# Sheet1.net
KiCad netlist of a schematic drawn in Altium Designer
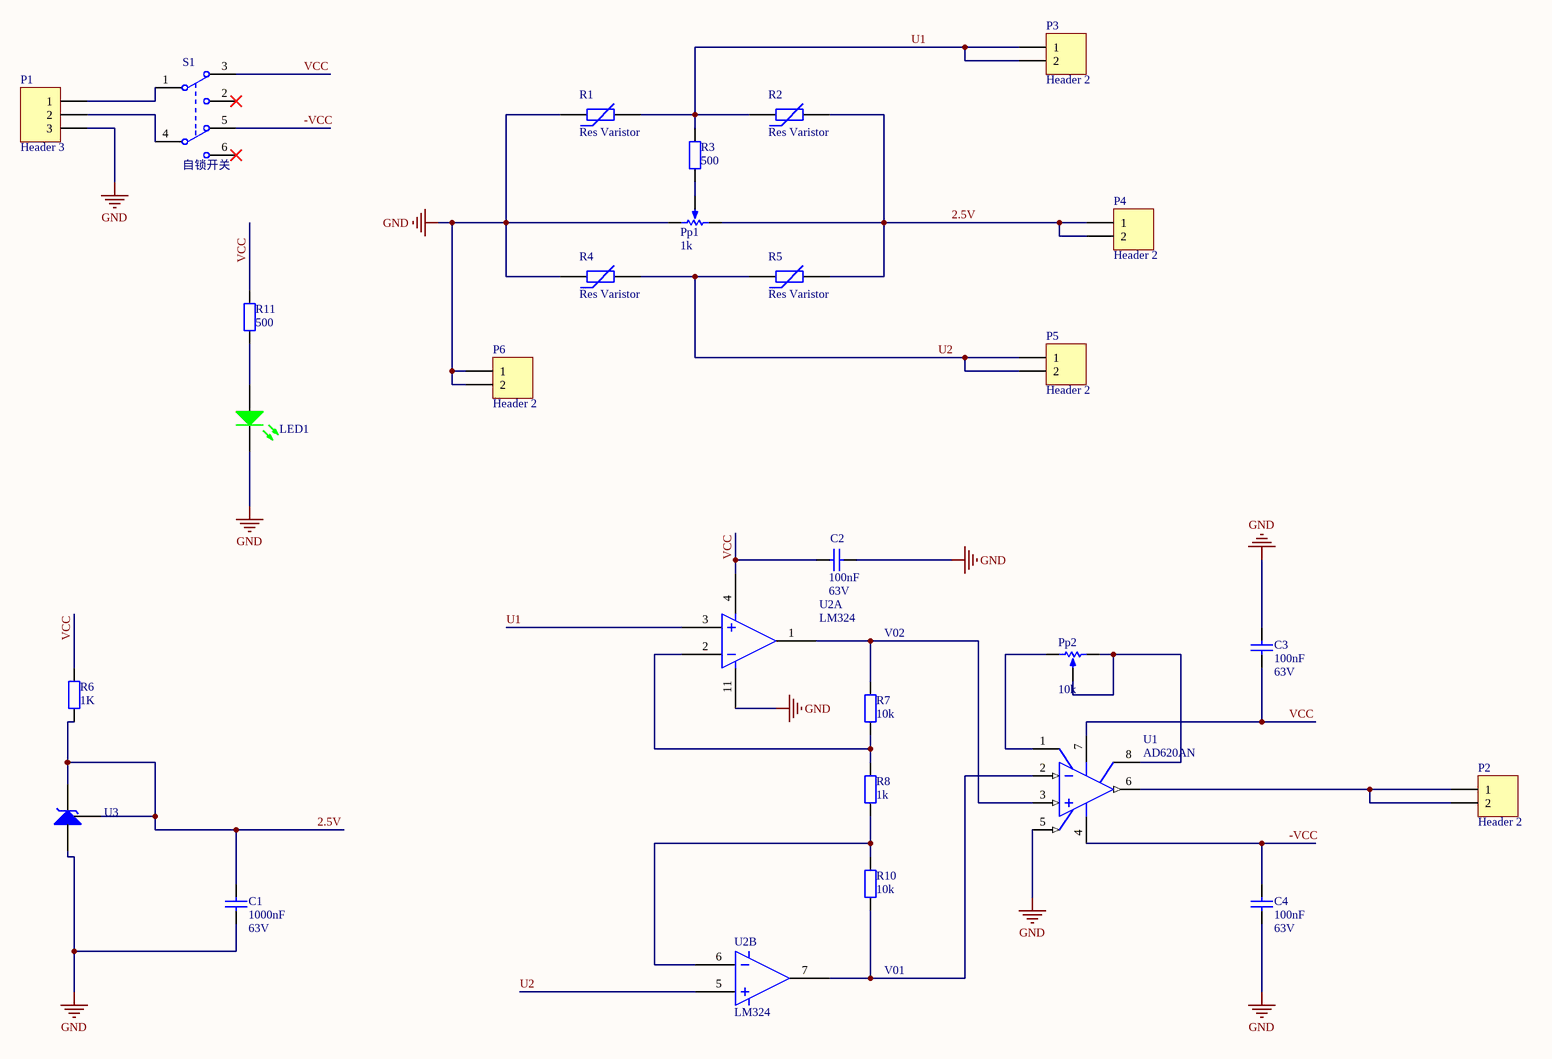
[diagram p0: Sheet1.SchDoc]

(export (version "E")
  (design (tool "Eeschema 10.0.6"))
  (components
    (comp (ref "C1")
      (value "1000nF")
      (footprint "Capacitor-Disk-Middle")
      (description "CBB聚乙烯薄膜电容")
      (fields
        (field (name "VOLTAGE") "63V")
        (field (name "Comment") "Cap Nicklon")
        (field (name "PUBLISHER") "Altium Limited")
      )
      (libsource (lib "02-Miscellaneous_Devices_ZSF_Library") (part "Cap Nicklon"))
    )
    (comp (ref "C2")
      (value "100nF")
      (footprint "Capacitor-Disk-Middle")
      (description "CBB聚乙烯薄膜电容")
      (fields
        (field (name "VOLTAGE") "63V")
        (field (name "Comment") "Cap Nicklon")
        (field (name "PUBLISHER") "Altium Limited")
      )
      (libsource (lib "02-Miscellaneous_Devices_ZSF_Library") (part "Cap Nicklon"))
    )
    (comp (ref "C3")
      (value "100nF")
      (footprint "Capacitor-Disk-Middle")
      (description "CBB聚乙烯薄膜电容")
      (fields
        (field (name "VOLTAGE") "63V")
        (field (name "Comment") "Cap Nicklon")
        (field (name "PUBLISHER") "Altium Limited")
      )
      (libsource (lib "02-Miscellaneous_Devices_ZSF_Library") (part "Cap Nicklon"))
    )
    (comp (ref "C4")
      (value "100nF")
      (footprint "Capacitor-Disk-Middle")
      (description "CBB聚乙烯薄膜电容")
      (fields
        (field (name "VOLTAGE") "63V")
        (field (name "Comment") "Cap Nicklon")
        (field (name "PUBLISHER") "Altium Limited")
      )
      (libsource (lib "02-Miscellaneous_Devices_ZSF_Library") (part "Cap Nicklon"))
    )
    (comp (ref "LED1")
      (value "LED-3-G")
      (footprint "LED-R3-H5-SINGLE-G")
      (description "Typical INFRARED GaAs LED")
      (fields (field (name "PUBLISHER") "Altium Limited"))
      (libsource (lib "03-EButterflyIntegratedLibrary") (part "LED-3-G"))
    )
    (comp (ref "P1")
      (value "Header 3")
      (footprint "HX2.54-3")
      (description "Header, 3-Pin")
      (fields (field (name "PUBLISHER") "Altium Limited"))
      (libsource (lib "03-EButterflyIntegratedLibrary") (part "Header 3"))
    )
    (comp (ref "P2")
      (value "Header 2")
      (footprint "HDR1X2")
      (description "Header, 2-Pin")
      (fields (field (name "PUBLISHER") "Altium Limited"))
      (libsource (lib "03-EButterflyIntegratedLibrary") (part "Header 2"))
    )
    (comp (ref "P3")
      (value "Header 2")
      (footprint "HDR1X2")
      (description "Header, 2-Pin")
      (fields (field (name "PUBLISHER") "Altium Limited"))
      (libsource (lib "03-EButterflyIntegratedLibrary") (part "Header 2"))
    )
    (comp (ref "P4")
      (value "Header 2")
      (footprint "HDR1X2")
      (description "Header, 2-Pin")
      (fields (field (name "PUBLISHER") "Altium Limited"))
      (libsource (lib "03-EButterflyIntegratedLibrary") (part "Header 2"))
    )
    (comp (ref "P5")
      (value "Header 2")
      (footprint "HDR1X2")
      (description "Header, 2-Pin")
      (fields (field (name "PUBLISHER") "Altium Limited"))
      (libsource (lib "03-EButterflyIntegratedLibrary") (part "Header 2"))
    )
    (comp (ref "P6")
      (value "Header 2")
      (footprint "HDR1X2")
      (description "Header, 2-Pin")
      (fields (field (name "PUBLISHER") "Altium Limited"))
      (libsource (lib "03-EButterflyIntegratedLibrary") (part "Header 2"))
    )
    (comp (ref "Pp1")
      (value "1k")
      (footprint "RP_3296")
      (description "3296电位器")
      (libsource (lib "02-Miscellaneous_Devices_ZSF_Library") (part "RP_3296"))
    )
    (comp (ref "Pp2")
      (value "10k")
      (footprint "RP_3296")
      (description "3296电位器")
      (libsource (lib "02-Miscellaneous_Devices_ZSF_Library") (part "RP_3296"))
    )
    (comp (ref "R1")
      (value "Res Varistor")
      (footprint "RESC2012N")
      (description "贴片压敏电阻")
      (fields (field (name "PUBLISHER") "Altium Limited"))
      (libsource (lib "02-Miscellaneous_Devices_ZSF_Library") (part "Res Varistor"))
    )
    (comp (ref "R2")
      (value "Res Varistor")
      (footprint "RESC2012N")
      (description "贴片压敏电阻")
      (fields (field (name "PUBLISHER") "Altium Limited"))
      (libsource (lib "02-Miscellaneous_Devices_ZSF_Library") (part "Res Varistor"))
    )
    (comp (ref "R3")
      (value "500")
      (footprint "AXIAL-0.3")
      (description "Resistor")
      (fields (field (name "PUBLISHER") "Altium Limited"))
      (libsource (lib "03-EButterflyIntegratedLibrary") (part "Resistor"))
    )
    (comp (ref "R4")
      (value "Res Varistor")
      (footprint "RESC2012N")
      (description "贴片压敏电阻")
      (fields (field (name "PUBLISHER") "Altium Limited"))
      (libsource (lib "02-Miscellaneous_Devices_ZSF_Library") (part "Res Varistor"))
    )
    (comp (ref "R5")
      (value "Res Varistor")
      (footprint "RESC2012N")
      (description "贴片压敏电阻")
      (fields (field (name "PUBLISHER") "Altium Limited"))
      (libsource (lib "02-Miscellaneous_Devices_ZSF_Library") (part "Res Varistor"))
    )
    (comp (ref "R6")
      (value "1K")
      (footprint "AXIAL-0.3")
      (description "Resistor")
      (fields (field (name "PUBLISHER") "Altium Limited"))
      (libsource (lib "") (part "Resistor_1"))
    )
    (comp (ref "R7")
      (value "10k")
      (footprint "AXIAL-0.3")
      (description "Resistor")
      (fields (field (name "PUBLISHER") "Altium Limited"))
      (libsource (lib "03-EButterflyIntegratedLibrary") (part "Resistor"))
    )
    (comp (ref "R8")
      (value "1k")
      (footprint "AXIAL-0.3")
      (description "Resistor")
      (fields (field (name "PUBLISHER") "Altium Limited"))
      (libsource (lib "03-EButterflyIntegratedLibrary") (part "Resistor"))
    )
    (comp (ref "R10")
      (value "10k")
      (footprint "AXIAL-0.3")
      (description "Resistor")
      (fields (field (name "PUBLISHER") "Altium Limited"))
      (libsource (lib "03-EButterflyIntegratedLibrary") (part "Resistor"))
    )
    (comp (ref "R11")
      (value "500")
      (footprint "AXIAL-0.3")
      (description "Resistor")
      (fields (field (name "PUBLISHER") "Altium Limited"))
      (libsource (lib "") (part "Resistor_1"))
    )
    (comp (ref "S1")
      (value "自锁开关")
      (footprint "sw_8.5mm")
      (libsource (lib "02-Miscellaneous_Devices_ZSF_Library") (part "SW DPDT"))
    )
    (comp (ref "U1")
      (value "AD620AN")
      (footprint "N-8")
      (description "Low-Cost, Low-Power Instrumentation Amplifier")
      (fields (field (name "PUBLISHER") "Altium Limited"))
      (libsource (lib "AD Instrumentation Amplifier") (part "AD620AN"))
    )
    (comp (ref "U2") (value "LM324") (footprint "DIP-14") (libsource (lib "模拟集成电路") (part "LM324")))
    (comp (ref "U3")
      (value "TL431")
      (footprint "BCY-W3/E4")
      (libsource (lib "03-EButterflyIntegratedLibrary") (part "TL431"))
    )
  )
  (nets
    (net (code "1") (name "/-VCC") (class "Default")
      (node (ref "C4") (pin "2") (pinfunction "2_2") (pintype "passive"))
      (node (ref "S1") (pin "5") (pinfunction "5_5") (pintype "passive"))
      (node (ref "U1") (pin "4") (pinfunction "V-_4") (pintype "power_in"))
    )
    (net (code "2") (name "/2.5V") (class "Default")
      (node (ref "C1") (pin "2") (pinfunction "2_2") (pintype "passive"))
      (node (ref "P4") (pin "1") (pinfunction "1_1") (pintype "passive"))
      (node (ref "P4") (pin "2") (pinfunction "2_2") (pintype "passive"))
      (node (ref "Pp1") (pin "1") (pinfunction "TOP_1") (pintype "passive"))
      (node (ref "R2") (pin "2") (pinfunction "2_2") (pintype "passive"))
      (node (ref "R5") (pin "2") (pinfunction "2_2") (pintype "passive"))
      (node (ref "R6") (pin "1") (pinfunction "1_1") (pintype "passive"))
      (node (ref "U3") (pin "1") (pinfunction "R_1") (pintype "passive"))
      (node (ref "U3") (pin "3") (pinfunction "K_3") (pintype "passive"))
    )
    (net (code "3") (name "/U1") (class "Default")
      (node (ref "P3") (pin "1") (pinfunction "1_1") (pintype "passive"))
      (node (ref "P3") (pin "2") (pinfunction "2_2") (pintype "passive"))
      (node (ref "R1") (pin "2") (pinfunction "2_2") (pintype "passive"))
      (node (ref "R2") (pin "1") (pinfunction "1_1") (pintype "passive"))
      (node (ref "R3") (pin "1") (pinfunction "1_1") (pintype "passive"))
      (node (ref "U2") (pin "3") (pintype "passive"))
    )
    (net (code "4") (name "/U2") (class "Default")
      (node (ref "P5") (pin "1") (pinfunction "1_1") (pintype "passive"))
      (node (ref "P5") (pin "2") (pinfunction "2_2") (pintype "passive"))
      (node (ref "R4") (pin "2") (pinfunction "2_2") (pintype "passive"))
      (node (ref "R5") (pin "1") (pinfunction "1_1") (pintype "passive"))
      (node (ref "U2") (pin "5") (pintype "passive"))
    )
    (net (code "5") (name "/VCC") (class "Default")
      (node (ref "C2") (pin "2") (pinfunction "2_2") (pintype "passive"))
      (node (ref "C3") (pin "2") (pinfunction "2_2") (pintype "passive"))
      (node (ref "R11") (pin "2") (pinfunction "2_2") (pintype "passive"))
      (node (ref "R6") (pin "2") (pinfunction "2_2") (pintype "passive"))
      (node (ref "S1") (pin "3") (pinfunction "3_3") (pintype "passive"))
      (node (ref "U1") (pin "7") (pinfunction "V+_7") (pintype "power_in"))
      (node (ref "U2") (pin "4") (pintype "passive"))
    )
    (net (code "6") (name "GND") (class "Default")
      (node (ref "C1") (pin "1") (pinfunction "1_1") (pintype "passive"))
      (node (ref "C2") (pin "1") (pinfunction "1_1") (pintype "passive"))
      (node (ref "C3") (pin "1") (pinfunction "1_1") (pintype "passive"))
      (node (ref "C4") (pin "1") (pinfunction "1_1") (pintype "passive"))
      (node (ref "LED1") (pin "2") (pinfunction "K_2") (pintype "passive"))
      (node (ref "P1") (pin "3") (pinfunction "3_3") (pintype "passive"))
      (node (ref "P6") (pin "1") (pinfunction "1_1") (pintype "passive"))
      (node (ref "P6") (pin "2") (pinfunction "2_2") (pintype "passive"))
      (node (ref "Pp1") (pin "3") (pinfunction "BOT_3") (pintype "passive"))
      (node (ref "R1") (pin "1") (pinfunction "1_1") (pintype "passive"))
      (node (ref "R4") (pin "1") (pinfunction "1_1") (pintype "passive"))
      (node (ref "U1") (pin "5") (pinfunction "REF_5") (pintype "input"))
      (node (ref "U2") (pin "11") (pintype "passive"))
      (node (ref "U3") (pin "2") (pinfunction "A_2") (pintype "passive"))
    )
    (net (code "7") (name "Net-(LED1-A)") (class "Default")
      (node (ref "LED1") (pin "1") (pinfunction "A_1") (pintype "passive"))
      (node (ref "R11") (pin "1") (pinfunction "1_1") (pintype "passive"))
    )
    (net (code "8") (name "Net-(P1-Pad1)") (class "Default")
      (node (ref "P1") (pin "1") (pinfunction "1_1") (pintype "passive"))
      (node (ref "S1") (pin "1") (pinfunction "1_1") (pintype "passive"))
    )
    (net (code "9") (name "Net-(P1-Pad2)") (class "Default")
      (node (ref "P1") (pin "2") (pinfunction "2_2") (pintype "passive"))
      (node (ref "S1") (pin "4") (pinfunction "4_4") (pintype "passive"))
    )
    (net (code "10") (name "Net-(Pp1-TAP)") (class "Default")
      (node (ref "Pp1") (pin "2") (pinfunction "TAP_2") (pintype "passive"))
      (node (ref "R3") (pin "2") (pinfunction "2_2") (pintype "passive"))
    )
    (net (code "11") (name "Net-(Pp2-BOT)") (class "Default")
      (node (ref "Pp2") (pin "2") (pinfunction "TAP_2") (pintype "passive"))
      (node (ref "Pp2") (pin "3") (pinfunction "BOT_3") (pintype "passive"))
      (node (ref "U1") (pin "8") (pinfunction "RG_8") (pintype "passive"))
    )
    (net (code "12") (name "Net-(Pp2-TOP)") (class "Default")
      (node (ref "Pp2") (pin "1") (pinfunction "TOP_1") (pintype "passive"))
      (node (ref "U1") (pin "1") (pinfunction "RG_1") (pintype "passive"))
    )
    (net (code "13") (name "Net-(R7-Pad2)") (class "Default")
      (node (ref "R7") (pin "2") (pinfunction "2_2") (pintype "passive"))
      (node (ref "R8") (pin "1") (pinfunction "1_1") (pintype "passive"))
      (node (ref "U2") (pin "2") (pintype "passive"))
    )
    (net (code "14") (name "Net-(R10-Pad1)") (class "Default")
      (node (ref "R10") (pin "1") (pinfunction "1_1") (pintype "passive"))
      (node (ref "R8") (pin "2") (pinfunction "2_2") (pintype "passive"))
      (node (ref "U2") (pin "6") (pintype "passive"))
    )
    (net (code "15") (name "Net-(U1-+IN)") (class "Default")
      (node (ref "R7") (pin "1") (pinfunction "1_1") (pintype "passive"))
      (node (ref "U1") (pin "3") (pinfunction "+IN_3") (pintype "input"))
      (node (ref "U2") (pin "1") (pintype "passive"))
    )
    (net (code "16") (name "Net-(U1--IN)") (class "Default")
      (node (ref "R10") (pin "2") (pinfunction "2_2") (pintype "passive"))
      (node (ref "U1") (pin "2") (pinfunction "-IN_2") (pintype "input"))
      (node (ref "U2") (pin "7") (pintype "passive"))
    )
    (net (code "17") (name "Net-(U1-OUT)") (class "Default")
      (node (ref "P2") (pin "1") (pinfunction "1_1") (pintype "passive"))
      (node (ref "P2") (pin "2") (pinfunction "2_2") (pintype "passive"))
      (node (ref "U1") (pin "6") (pinfunction "OUT_6") (pintype "output"))
    )
    (net (code "18") (name "unconnected-(S1-Pad2)") (class "Default")
      (node (ref "S1") (pin "2") (pinfunction "2_2") (pintype "passive+no_connect"))
    )
    (net (code "19") (name "unconnected-(S1-Pad6)") (class "Default")
      (node (ref "S1") (pin "6") (pinfunction "6_6") (pintype "passive+no_connect"))
    )
  )
)
